# reactor.net
KiCad netlist of a schematic drawn in EAGLE
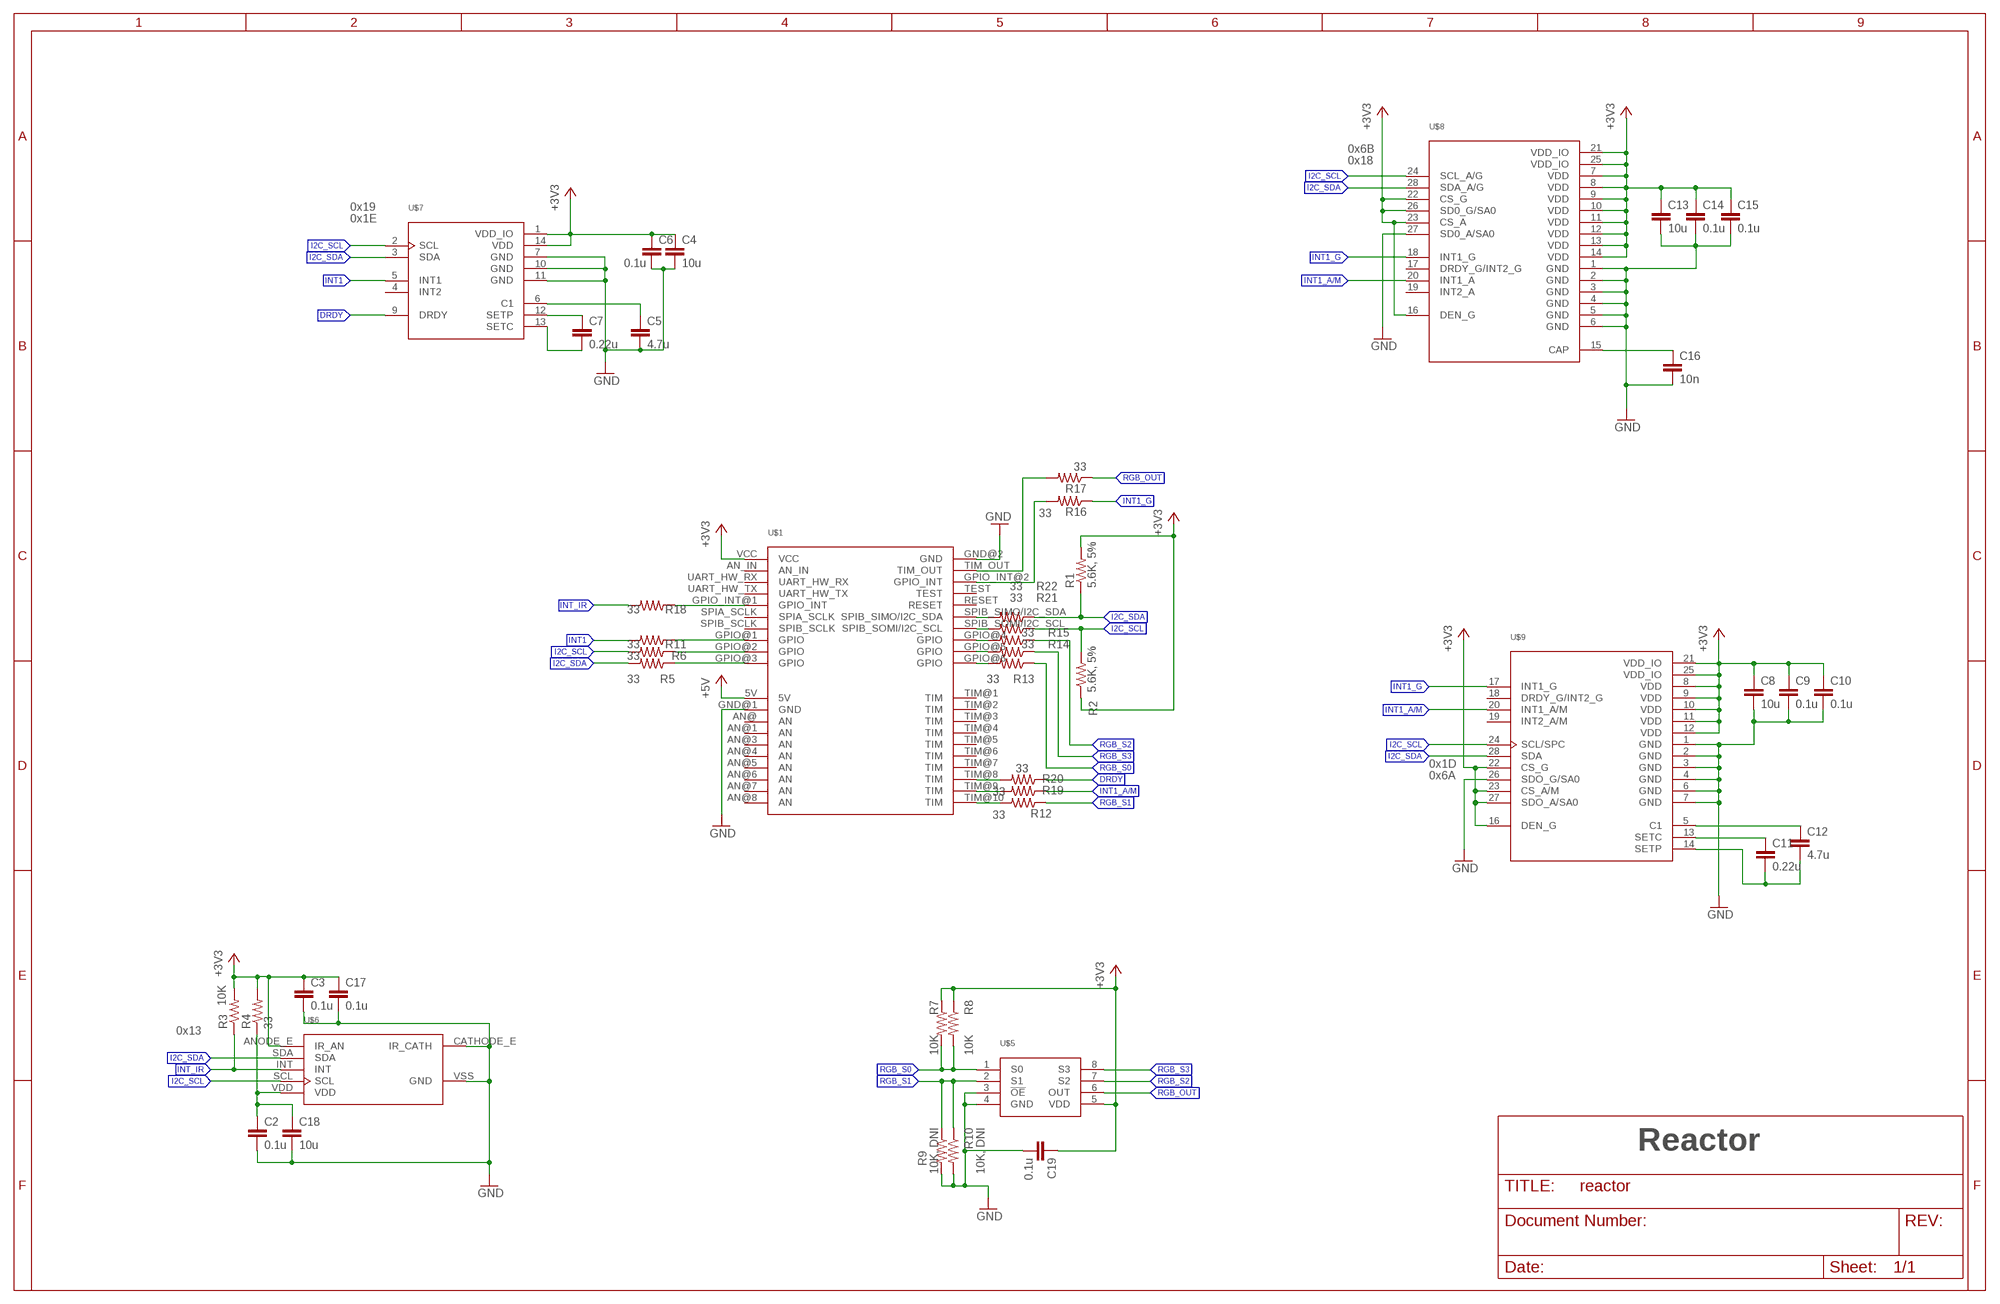
[diagram p0: schematic, sheet 1]

(export (version "E")
  (design (tool "Eeschema 10.0.6"))
  (components
    (comp (ref "C2")
      (value "0.1u")
      (footprint "eagle-import:C0603")
      (fields (field (name "MPN") "VJ0603V104ZXXCW1BC"))
      (libsource (lib "eagle-import") (part "C-EUC0603"))
    )
    (comp (ref "C3")
      (value "0.1u")
      (footprint "eagle-import:C0603")
      (fields (field (name "MPN") "VJ0603V104ZXXCW1BC"))
      (libsource (lib "eagle-import") (part "C-EUC0603"))
    )
    (comp (ref "C4")
      (value "10u")
      (footprint "eagle-import:C0603")
      (fields (field (name "MPN") "LMK107BBJ106MALT"))
      (libsource (lib "eagle-import") (part "C-EUC0603"))
    )
    (comp (ref "C5")
      (value "4.7u")
      (footprint "eagle-import:C0603")
      (fields (field (name "MPN") "GRM188F51A475ZE20J"))
      (libsource (lib "eagle-import") (part "C-EUC0603"))
    )
    (comp (ref "C6")
      (value "0.1u")
      (footprint "eagle-import:C0603")
      (fields (field (name "MPN") "VJ0603V104ZXXCW1BC"))
      (libsource (lib "eagle-import") (part "C-EUC0603"))
    )
    (comp (ref "C7")
      (value "0.22u")
      (footprint "eagle-import:C0603")
      (fields (field (name "MPN") "VJ0603V224MXJPW1BC"))
      (libsource (lib "eagle-import") (part "C-EUC0603"))
    )
    (comp (ref "C8")
      (value "10u")
      (footprint "eagle-import:C0603")
      (fields (field (name "MPN") "LMK107BBJ106MALT"))
      (libsource (lib "eagle-import") (part "C-EUC0603"))
    )
    (comp (ref "C9")
      (value "0.1u")
      (footprint "eagle-import:C0603")
      (fields (field (name "MPN") "VJ0603V104ZXXCW1BC"))
      (libsource (lib "eagle-import") (part "C-EUC0603"))
    )
    (comp (ref "C10")
      (value "0.1u")
      (footprint "eagle-import:C0603")
      (fields (field (name "MPN") "VJ0603V104ZXXCW1BC"))
      (libsource (lib "eagle-import") (part "C-EUC0603"))
    )
    (comp (ref "C11")
      (value "0.22u")
      (footprint "eagle-import:C0603")
      (fields (field (name "MPN") "VJ0603V224MXJPW1BC"))
      (libsource (lib "eagle-import") (part "C-EUC0603"))
    )
    (comp (ref "C12")
      (value "4.7u")
      (footprint "eagle-import:C0603")
      (fields (field (name "MPN") "GRM188F51A475ZE20J"))
      (libsource (lib "eagle-import") (part "C-EUC0603"))
    )
    (comp (ref "C13")
      (value "10u")
      (footprint "eagle-import:C0603")
      (fields (field (name "MPN") "LMK107BBJ106MALT"))
      (libsource (lib "eagle-import") (part "C-EUC0603"))
    )
    (comp (ref "C14")
      (value "0.1u")
      (footprint "eagle-import:C0603")
      (fields (field (name "MPN") "VJ0603V104ZXXCW1BC"))
      (libsource (lib "eagle-import") (part "C-EUC0603"))
    )
    (comp (ref "C15")
      (value "0.1u")
      (footprint "eagle-import:C0603")
      (fields (field (name "MPN") "VJ0603V104ZXXCW1BC"))
      (libsource (lib "eagle-import") (part "C-EUC0603"))
    )
    (comp (ref "C16")
      (value "10n")
      (footprint "eagle-import:C0603")
      (fields (field (name "MPN") "VJ0603Y103KXACW1BC"))
      (libsource (lib "eagle-import") (part "C-EUC0603"))
    )
    (comp (ref "C17")
      (value "0.1u")
      (footprint "eagle-import:C0603")
      (fields (field (name "MPN") "LMK107BBJ106MALT"))
      (libsource (lib "eagle-import") (part "C-EUC0603"))
    )
    (comp (ref "C18")
      (value "10u")
      (footprint "eagle-import:C0603")
      (fields (field (name "MPN") "LMK107BBJ106MALT"))
      (libsource (lib "eagle-import") (part "C-EUC0603"))
    )
    (comp (ref "C19")
      (value "0.1u")
      (footprint "eagle-import:C0603")
      (fields (field (name "MPN") "VJ0603V104ZXXCW1BC"))
      (libsource (lib "eagle-import") (part "C-EUC0603"))
    )
    (comp (ref "R1")
      (value "5.6K, 5%")
      (footprint "eagle-import:R0603")
      (fields (field (name "MPN") "RK73B1JTTDD562J"))
      (libsource (lib "eagle-import") (part "R-US_R0603"))
    )
    (comp (ref "R2")
      (value "5.6K, 5%")
      (footprint "eagle-import:R0603")
      (fields (field (name "MPN") "RK73B1JTTDD562J"))
      (libsource (lib "eagle-import") (part "R-US_R0603"))
    )
    (comp (ref "R3")
      (value "10K")
      (footprint "eagle-import:R0603")
      (fields (field (name "MPN") "WR06X1002FTL"))
      (libsource (lib "eagle-import") (part "R-US_R0603"))
    )
    (comp (ref "R4")
      (value "33")
      (footprint "eagle-import:R0603")
      (fields (field (name "MPN") "CR0402-JW-330GLF"))
      (libsource (lib "eagle-import") (part "R-US_R0603"))
    )
    (comp (ref "R5")
      (value "33")
      (footprint "eagle-import:R0603")
      (fields (field (name "MPN") "CR0402-JW-330GLF"))
      (libsource (lib "eagle-import") (part "R-US_R0603"))
    )
    (comp (ref "R6")
      (value "33")
      (footprint "eagle-import:R0603")
      (fields (field (name "MPN") "CR0402-JW-330GLF"))
      (libsource (lib "eagle-import") (part "R-US_R0603"))
    )
    (comp (ref "R7")
      (value "10K")
      (footprint "eagle-import:R0603")
      (fields (field (name "MPN") "WR06X1002FTL"))
      (libsource (lib "eagle-import") (part "R-US_R0603"))
    )
    (comp (ref "R8")
      (value "10K")
      (footprint "eagle-import:R0603")
      (fields (field (name "MPN") "WR06X1002FTL"))
      (libsource (lib "eagle-import") (part "R-US_R0603"))
    )
    (comp (ref "R9")
      (value "10K, DNI")
      (footprint "eagle-import:R0603")
      (fields (field (name "MPN") "WR06X1002FTL"))
      (libsource (lib "eagle-import") (part "R-US_R0603"))
    )
    (comp (ref "R10")
      (value "10K, DNI")
      (footprint "eagle-import:R0603")
      (fields (field (name "MPN") "WR06X1002FTL"))
      (libsource (lib "eagle-import") (part "R-US_R0603"))
    )
    (comp (ref "R11")
      (value "33")
      (footprint "eagle-import:R0603")
      (fields (field (name "MPN") "CR0402-JW-330GLF"))
      (libsource (lib "eagle-import") (part "R-US_R0603"))
    )
    (comp (ref "R12")
      (value "33")
      (footprint "eagle-import:R0603")
      (fields (field (name "MPN") "CR0402-JW-330GLF"))
      (libsource (lib "eagle-import") (part "R-US_R0603"))
    )
    (comp (ref "R13")
      (value "33")
      (footprint "eagle-import:R0603")
      (fields (field (name "MPN") "CR0402-JW-330GLF"))
      (libsource (lib "eagle-import") (part "R-US_R0603"))
    )
    (comp (ref "R14")
      (value "33")
      (footprint "eagle-import:R0603")
      (fields (field (name "MPN") "CR0402-JW-330GLF"))
      (libsource (lib "eagle-import") (part "R-US_R0603"))
    )
    (comp (ref "R15")
      (value "33")
      (footprint "eagle-import:R0603")
      (fields (field (name "MPN") "CR0402-JW-330GLF"))
      (libsource (lib "eagle-import") (part "R-US_R0603"))
    )
    (comp (ref "R16")
      (value "33")
      (footprint "eagle-import:R0603")
      (fields (field (name "MPN") "CR0402-JW-330GLF"))
      (libsource (lib "eagle-import") (part "R-US_R0603"))
    )
    (comp (ref "R17")
      (value "33")
      (footprint "eagle-import:R0603")
      (fields (field (name "MPN") "CR0402-JW-330GLF"))
      (libsource (lib "eagle-import") (part "R-US_R0603"))
    )
    (comp (ref "R18")
      (value "33")
      (footprint "eagle-import:R0603")
      (fields (field (name "MPN") "CR0402-JW-330GLF"))
      (libsource (lib "eagle-import") (part "R-US_R0603"))
    )
    (comp (ref "R19")
      (value "33")
      (footprint "eagle-import:R0603")
      (fields (field (name "MPN") "CR0402-JW-330GLF"))
      (libsource (lib "eagle-import") (part "R-US_R0603"))
    )
    (comp (ref "R20")
      (value "33")
      (footprint "eagle-import:R0603")
      (fields (field (name "MPN") "CR0402-JW-330GLF"))
      (libsource (lib "eagle-import") (part "R-US_R0603"))
    )
    (comp (ref "R21")
      (value "33")
      (footprint "eagle-import:R0603")
      (fields (field (name "MPN") "CR0402-JW-330GLF"))
      (libsource (lib "eagle-import") (part "R-US_R0603"))
    )
    (comp (ref "R22")
      (value "33")
      (footprint "eagle-import:R0603")
      (fields (field (name "MPN") "CR0402-JW-330GLF"))
      (libsource (lib "eagle-import") (part "R-US_R0603"))
    )
    (comp (ref "U$1")
      (value "LAUNCHPAD_BOOSTER_PACK")
      (footprint "eagle-import:LAUNCHPAD_BOOSTER_PACK")
      (libsource (lib "eagle-import") (part "LAUNCHPAD_BOOSTER_PACK"))
    )
    (comp (ref "U$5")
      (value "TCS32X0")
      (footprint "eagle-import:SOIC8")
      (libsource (lib "eagle-import") (part "TCS32X0"))
    )
    (comp (ref "U$6")
      (value "VCNL3020")
      (footprint "eagle-import:VCNL3020")
      (libsource (lib "eagle-import") (part "VCNL3020"))
    )
    (comp (ref "U$7")
      (value "LSM303DLHC")
      (footprint "eagle-import:LGA14")
      (libsource (lib "eagle-import") (part "LSM303DLHC"))
    )
    (comp (ref "U$8")
      (value "LSM330DLC")
      (footprint "eagle-import:LGA28-4X5")
      (libsource (lib "eagle-import") (part "LSM330DLC"))
    )
    (comp (ref "U$9")
      (value "LSM333D")
      (footprint "eagle-import:LGA28")
      (libsource (lib "eagle-import") (part "LSM333D"))
    )
  )
  (nets
    (net (code "1") (name "+3V3") (class "Default")
      (node (ref "C10") (pin "1") (pinfunction "1_1") (pintype "passive"))
      (node (ref "C13") (pin "1") (pinfunction "1_1") (pintype "passive"))
      (node (ref "C14") (pin "1") (pinfunction "1_1") (pintype "passive"))
      (node (ref "C15") (pin "1") (pinfunction "1_1") (pintype "passive"))
      (node (ref "C17") (pin "1") (pinfunction "1_1") (pintype "passive"))
      (node (ref "C19") (pin "1") (pinfunction "1_1") (pintype "passive"))
      (node (ref "C3") (pin "1") (pinfunction "1_1") (pintype "passive"))
      (node (ref "C4") (pin "1") (pinfunction "1_1") (pintype "passive"))
      (node (ref "C6") (pin "1") (pinfunction "1_1") (pintype "passive"))
      (node (ref "C8") (pin "1") (pinfunction "1_1") (pintype "passive"))
      (node (ref "C9") (pin "1") (pinfunction "1_1") (pintype "passive"))
      (node (ref "R1") (pin "2") (pinfunction "2_2") (pintype "passive"))
      (node (ref "R2") (pin "1") (pinfunction "1_1") (pintype "passive"))
      (node (ref "R3") (pin "2") (pinfunction "2_2") (pintype "passive"))
      (node (ref "R4") (pin "2") (pinfunction "2_2") (pintype "passive"))
      (node (ref "R7") (pin "1") (pinfunction "1_1") (pintype "passive"))
      (node (ref "R8") (pin "1") (pinfunction "1_1") (pintype "passive"))
      (node (ref "U$1") (pin "VCC") (pinfunction "VCC_VCC") (pintype "power_in"))
      (node (ref "U$5") (pin "5") (pinfunction "VDD_5") (pintype "power_in"))
      (node (ref "U$6") (pin "ANODE_E") (pinfunction "IR_AN_ANODE_E") (pintype "passive"))
      (node (ref "U$7") (pin "1") (pinfunction "VDD_IO_1") (pintype "power_in"))
      (node (ref "U$7") (pin "14") (pinfunction "VDD_14") (pintype "power_in"))
      (node (ref "U$8") (pin "10") (pinfunction "VDD_10") (pintype "power_in"))
      (node (ref "U$8") (pin "11") (pinfunction "VDD_11") (pintype "power_in"))
      (node (ref "U$8") (pin "12") (pinfunction "VDD_12") (pintype "power_in"))
      (node (ref "U$8") (pin "13") (pinfunction "VDD_13") (pintype "power_in"))
      (node (ref "U$8") (pin "14") (pinfunction "VDD_14") (pintype "power_in"))
      (node (ref "U$8") (pin "16") (pinfunction "DEN_G_16") (pintype "input"))
      (node (ref "U$8") (pin "21") (pinfunction "VDD_IO_21") (pintype "power_in"))
      (node (ref "U$8") (pin "22") (pinfunction "CS_G_22") (pintype "input"))
      (node (ref "U$8") (pin "23") (pinfunction "CS_A_23") (pintype "input"))
      (node (ref "U$8") (pin "25") (pinfunction "VDD_IO_25") (pintype "power_in"))
      (node (ref "U$8") (pin "26") (pinfunction "SD0_G/SA0_26") (pintype "bidirectional"))
      (node (ref "U$8") (pin "7") (pinfunction "VDD_7") (pintype "power_in"))
      (node (ref "U$8") (pin "8") (pinfunction "VDD_8") (pintype "power_in"))
      (node (ref "U$8") (pin "9") (pinfunction "VDD_9") (pintype "power_in"))
      (node (ref "U$9") (pin "10") (pinfunction "VDD_10") (pintype "power_in"))
      (node (ref "U$9") (pin "11") (pinfunction "VDD_11") (pintype "power_in"))
      (node (ref "U$9") (pin "12") (pinfunction "VDD_12") (pintype "power_in"))
      (node (ref "U$9") (pin "16") (pinfunction "DEN_G_16") (pintype "input"))
      (node (ref "U$9") (pin "21") (pinfunction "VDD_IO_21") (pintype "power_in"))
      (node (ref "U$9") (pin "22") (pinfunction "CS_G_22") (pintype "input"))
      (node (ref "U$9") (pin "23") (pinfunction "CS_A/M_23") (pintype "input"))
      (node (ref "U$9") (pin "25") (pinfunction "VDD_IO_25") (pintype "power_in"))
      (node (ref "U$9") (pin "27") (pinfunction "SDO_A/SA0_27") (pintype "bidirectional"))
      (node (ref "U$9") (pin "8") (pinfunction "VDD_8") (pintype "power_in"))
      (node (ref "U$9") (pin "9") (pinfunction "VDD_9") (pintype "power_in"))
    )
    (net (code "2") (name "+5V") (class "Default")
      (node (ref "U$1") (pin "5V") (pinfunction "5V_5V") (pintype "power_in"))
    )
    (net (code "3") (name "DRDY") (class "Default")
      (node (ref "R20") (pin "1") (pinfunction "1_1") (pintype "passive"))
      (node (ref "U$7") (pin "9") (pinfunction "DRDY_9") (pintype "output"))
    )
    (net (code "4") (name "GND") (class "Default")
      (node (ref "C10") (pin "2") (pinfunction "2_2") (pintype "passive"))
      (node (ref "C13") (pin "2") (pinfunction "2_2") (pintype "passive"))
      (node (ref "C14") (pin "2") (pinfunction "2_2") (pintype "passive"))
      (node (ref "C15") (pin "2") (pinfunction "2_2") (pintype "passive"))
      (node (ref "C16") (pin "2") (pinfunction "2_2") (pintype "passive"))
      (node (ref "C17") (pin "2") (pinfunction "2_2") (pintype "passive"))
      (node (ref "C18") (pin "2") (pinfunction "2_2") (pintype "passive"))
      (node (ref "C19") (pin "2") (pinfunction "2_2") (pintype "passive"))
      (node (ref "C2") (pin "2") (pinfunction "2_2") (pintype "passive"))
      (node (ref "C3") (pin "2") (pinfunction "2_2") (pintype "passive"))
      (node (ref "C4") (pin "2") (pinfunction "2_2") (pintype "passive"))
      (node (ref "C5") (pin "2") (pinfunction "2_2") (pintype "passive"))
      (node (ref "C6") (pin "2") (pinfunction "2_2") (pintype "passive"))
      (node (ref "C8") (pin "2") (pinfunction "2_2") (pintype "passive"))
      (node (ref "C9") (pin "2") (pinfunction "2_2") (pintype "passive"))
      (node (ref "R10") (pin "2") (pinfunction "2_2") (pintype "passive"))
      (node (ref "R9") (pin "2") (pinfunction "2_2") (pintype "passive"))
      (node (ref "U$1") (pin "GND@1") (pinfunction "GND_GND@1") (pintype "power_in"))
      (node (ref "U$1") (pin "GND@2") (pinfunction "GND_GND@2") (pintype "power_in"))
      (node (ref "U$5") (pin "3") (pinfunction "~{OE}_3") (pintype "input"))
      (node (ref "U$5") (pin "4") (pinfunction "GND_4") (pintype "power_in"))
      (node (ref "U$6") (pin "CATHODE_E") (pinfunction "IR_CATH_CATHODE_E") (pintype "passive"))
      (node (ref "U$6") (pin "VSS") (pinfunction "GND_VSS") (pintype "power_in"))
      (node (ref "U$7") (pin "10") (pinfunction "GND_10") (pintype "power_in"))
      (node (ref "U$7") (pin "11") (pinfunction "GND_11") (pintype "power_in"))
      (node (ref "U$7") (pin "7") (pinfunction "GND_7") (pintype "power_in"))
      (node (ref "U$8") (pin "1") (pinfunction "GND_1") (pintype "power_in"))
      (node (ref "U$8") (pin "2") (pinfunction "GND_2") (pintype "power_in"))
      (node (ref "U$8") (pin "27") (pinfunction "SD0_A/SA0_27") (pintype "bidirectional"))
      (node (ref "U$8") (pin "3") (pinfunction "GND_3") (pintype "power_in"))
      (node (ref "U$8") (pin "4") (pinfunction "GND_4") (pintype "power_in"))
      (node (ref "U$8") (pin "5") (pinfunction "GND_5") (pintype "power_in"))
      (node (ref "U$8") (pin "6") (pinfunction "GND_6") (pintype "power_in"))
      (node (ref "U$9") (pin "1") (pinfunction "GND_1") (pintype "power_in"))
      (node (ref "U$9") (pin "2") (pinfunction "GND_2") (pintype "power_in"))
      (node (ref "U$9") (pin "26") (pinfunction "SDO_G/SA0_26") (pintype "bidirectional"))
      (node (ref "U$9") (pin "3") (pinfunction "GND_3") (pintype "power_in"))
      (node (ref "U$9") (pin "4") (pinfunction "GND_4") (pintype "power_in"))
      (node (ref "U$9") (pin "6") (pinfunction "GND_6") (pintype "power_in"))
      (node (ref "U$9") (pin "7") (pinfunction "GND_7") (pintype "power_in"))
    )
    (net (code "5") (name "I2C_SCL") (class "Default")
      (node (ref "R2") (pin "2") (pinfunction "2_2") (pintype "passive"))
      (node (ref "R21") (pin "1") (pinfunction "1_1") (pintype "passive"))
      (node (ref "R6") (pin "2") (pinfunction "2_2") (pintype "passive"))
      (node (ref "U$6") (pin "SCL") (pinfunction "SCL_SCL") (pintype "input"))
      (node (ref "U$7") (pin "2") (pinfunction "SCL_2") (pintype "open_collector"))
      (node (ref "U$8") (pin "24") (pinfunction "SCL_A/G_24") (pintype "open_collector"))
      (node (ref "U$9") (pin "24") (pinfunction "SCL/SPC_24") (pintype "open_collector"))
    )
    (net (code "6") (name "I2C_SDA") (class "Default")
      (node (ref "R1") (pin "1") (pinfunction "1_1") (pintype "passive"))
      (node (ref "R22") (pin "1") (pinfunction "1_1") (pintype "passive"))
      (node (ref "R5") (pin "2") (pinfunction "2_2") (pintype "passive"))
      (node (ref "U$6") (pin "SDA") (pinfunction "SDA_SDA") (pintype "bidirectional"))
      (node (ref "U$7") (pin "3") (pinfunction "SDA_3") (pintype "open_collector"))
      (node (ref "U$8") (pin "28") (pinfunction "SDA_A/G_28") (pintype "open_collector"))
      (node (ref "U$9") (pin "28") (pinfunction "SDA_28") (pintype "open_collector"))
    )
    (net (code "7") (name "INT1") (class "Default")
      (node (ref "R11") (pin "2") (pinfunction "2_2") (pintype "passive"))
      (node (ref "U$7") (pin "5") (pinfunction "INT1_5") (pintype "output"))
    )
    (net (code "8") (name "INT1_A{slash}M") (class "Default")
      (node (ref "R19") (pin "1") (pinfunction "1_1") (pintype "passive"))
      (node (ref "U$8") (pin "20") (pinfunction "INT1_A_20") (pintype "output"))
      (node (ref "U$9") (pin "20") (pinfunction "INT1_A/M_20") (pintype "output"))
    )
    (net (code "9") (name "INT1_G") (class "Default")
      (node (ref "R16") (pin "1") (pinfunction "1_1") (pintype "passive"))
      (node (ref "U$8") (pin "18") (pinfunction "INT1_G_18") (pintype "output"))
      (node (ref "U$9") (pin "17") (pinfunction "INT1_G_17") (pintype "output"))
    )
    (net (code "10") (name "INT_IR") (class "Default")
      (node (ref "R18") (pin "2") (pinfunction "2_2") (pintype "passive"))
      (node (ref "R3") (pin "1") (pinfunction "1_1") (pintype "passive"))
      (node (ref "U$6") (pin "INT") (pinfunction "INT_INT") (pintype "output"))
    )
    (net (code "11") (name "Net-(C18-Pad1)") (class "Default")
      (node (ref "C18") (pin "1") (pinfunction "1_1") (pintype "passive"))
      (node (ref "C2") (pin "1") (pinfunction "1_1") (pintype "passive"))
      (node (ref "R4") (pin "1") (pinfunction "1_1") (pintype "passive"))
      (node (ref "U$6") (pin "VDD") (pinfunction "VDD_VDD") (pintype "power_in"))
    )
    (net (code "12") (name "Net-(R5-Pad1)") (class "Default")
      (node (ref "R5") (pin "1") (pinfunction "1_1") (pintype "passive"))
      (node (ref "U$1") (pin "GPIO@3") (pinfunction "GPIO_GPIO@3") (pintype "bidirectional"))
    )
    (net (code "13") (name "Net-(R6-Pad1)") (class "Default")
      (node (ref "R6") (pin "1") (pinfunction "1_1") (pintype "passive"))
      (node (ref "U$1") (pin "GPIO@2") (pinfunction "GPIO_GPIO@2") (pintype "bidirectional"))
    )
    (net (code "14") (name "Net-(R11-Pad1)") (class "Default")
      (node (ref "R11") (pin "1") (pinfunction "1_1") (pintype "passive"))
      (node (ref "U$1") (pin "GPIO@1") (pinfunction "GPIO_GPIO@1") (pintype "bidirectional"))
    )
    (net (code "15") (name "Net-(R12-Pad2)") (class "Default")
      (node (ref "R12") (pin "2") (pinfunction "2_2") (pintype "passive"))
      (node (ref "U$1") (pin "TIM@10") (pinfunction "TIM_TIM@10") (pintype "bidirectional"))
    )
    (net (code "16") (name "Net-(R13-Pad2)") (class "Default")
      (node (ref "R13") (pin "2") (pinfunction "2_2") (pintype "passive"))
      (node (ref "U$1") (pin "GPIO@6") (pinfunction "GPIO_GPIO@6") (pintype "bidirectional"))
    )
    (net (code "17") (name "Net-(R14-Pad2)") (class "Default")
      (node (ref "R14") (pin "2") (pinfunction "2_2") (pintype "passive"))
      (node (ref "U$1") (pin "GPIO@5") (pinfunction "GPIO_GPIO@5") (pintype "bidirectional"))
    )
    (net (code "18") (name "Net-(R15-Pad2)") (class "Default")
      (node (ref "R15") (pin "2") (pinfunction "2_2") (pintype "passive"))
      (node (ref "U$1") (pin "GPIO@4") (pinfunction "GPIO_GPIO@4") (pintype "bidirectional"))
    )
    (net (code "19") (name "Net-(R16-Pad2)") (class "Default")
      (node (ref "R16") (pin "2") (pinfunction "2_2") (pintype "passive"))
      (node (ref "U$1") (pin "GPIO_INT@2") (pinfunction "GPIO_INT_GPIO_INT@2") (pintype "bidirectional"))
    )
    (net (code "20") (name "Net-(R17-Pad2)") (class "Default")
      (node (ref "R17") (pin "2") (pinfunction "2_2") (pintype "passive"))
      (node (ref "U$1") (pin "TIM_OUT") (pinfunction "TIM_OUT_TIM_OUT") (pintype "bidirectional"))
    )
    (net (code "21") (name "Net-(R18-Pad1)") (class "Default")
      (node (ref "R18") (pin "1") (pinfunction "1_1") (pintype "passive"))
      (node (ref "U$1") (pin "GPIO_INT@1") (pinfunction "GPIO_INT_GPIO_INT@1") (pintype "bidirectional"))
    )
    (net (code "22") (name "Net-(R19-Pad2)") (class "Default")
      (node (ref "R19") (pin "2") (pinfunction "2_2") (pintype "passive"))
      (node (ref "U$1") (pin "TIM@9") (pinfunction "TIM_TIM@9") (pintype "bidirectional"))
    )
    (net (code "23") (name "Net-(R20-Pad2)") (class "Default")
      (node (ref "R20") (pin "2") (pinfunction "2_2") (pintype "passive"))
      (node (ref "U$1") (pin "TIM@8") (pinfunction "TIM_TIM@8") (pintype "bidirectional"))
    )
    (net (code "24") (name "Net-(R21-Pad2)") (class "Default")
      (node (ref "R21") (pin "2") (pinfunction "2_2") (pintype "passive"))
      (node (ref "U$1") (pin "SPIB_SOMI/I2C_SCL") (pinfunction "SPIB_SOMI/I2C_SCL_SPIB_SOMI/I2C_SCL") (pintype "bidirectional"))
    )
    (net (code "25") (name "Net-(R22-Pad2)") (class "Default")
      (node (ref "R22") (pin "2") (pinfunction "2_2") (pintype "passive"))
      (node (ref "U$1") (pin "SPIB_SIMO/I2C_SDA") (pinfunction "SPIB_SIMO/I2C_SDA_SPIB_SIMO/I2C_SDA") (pintype "bidirectional"))
    )
    (net (code "26") (name "Net-(U$7-C1)") (class "Default")
      (node (ref "C5") (pin "1") (pinfunction "1_1") (pintype "passive"))
      (node (ref "U$7") (pin "6") (pinfunction "C1_6") (pintype "passive"))
    )
    (net (code "27") (name "Net-(U$7-SETC)") (class "Default")
      (node (ref "C7") (pin "2") (pinfunction "2_2") (pintype "passive"))
      (node (ref "U$7") (pin "13") (pinfunction "SETC_13") (pintype "passive"))
    )
    (net (code "28") (name "Net-(U$7-SETP)") (class "Default")
      (node (ref "C7") (pin "1") (pinfunction "1_1") (pintype "passive"))
      (node (ref "U$7") (pin "12") (pinfunction "SETP_12") (pintype "passive"))
    )
    (net (code "29") (name "Net-(U$8-CAP)") (class "Default")
      (node (ref "C16") (pin "1") (pinfunction "1_1") (pintype "passive"))
      (node (ref "U$8") (pin "15") (pinfunction "CAP_15") (pintype "passive"))
    )
    (net (code "30") (name "Net-(U$9-C1)") (class "Default")
      (node (ref "C12") (pin "1") (pinfunction "1_1") (pintype "passive"))
      (node (ref "U$9") (pin "5") (pinfunction "C1_5") (pintype "passive"))
    )
    (net (code "31") (name "Net-(U$9-SETC)") (class "Default")
      (node (ref "C11") (pin "1") (pinfunction "1_1") (pintype "passive"))
      (node (ref "U$9") (pin "13") (pinfunction "SETC_13") (pintype "passive"))
    )
    (net (code "32") (name "Net-(U$9-SETP)") (class "Default")
      (node (ref "C11") (pin "2") (pinfunction "2_2") (pintype "passive"))
      (node (ref "C12") (pin "2") (pinfunction "2_2") (pintype "passive"))
      (node (ref "U$9") (pin "14") (pinfunction "SETP_14") (pintype "passive"))
    )
    (net (code "33") (name "RGB_OUT") (class "Default")
      (node (ref "R17") (pin "1") (pinfunction "1_1") (pintype "passive"))
      (node (ref "U$5") (pin "6") (pinfunction "OUT_6") (pintype "output"))
    )
    (net (code "34") (name "RGB_S0") (class "Default")
      (node (ref "R13") (pin "1") (pinfunction "1_1") (pintype "passive"))
      (node (ref "R7") (pin "2") (pinfunction "2_2") (pintype "passive"))
      (node (ref "R8") (pin "2") (pinfunction "2_2") (pintype "passive"))
      (node (ref "U$5") (pin "1") (pinfunction "S0_1") (pintype "input"))
    )
    (net (code "35") (name "RGB_S1") (class "Default")
      (node (ref "R10") (pin "1") (pinfunction "1_1") (pintype "passive"))
      (node (ref "R12") (pin "1") (pinfunction "1_1") (pintype "passive"))
      (node (ref "R9") (pin "1") (pinfunction "1_1") (pintype "passive"))
      (node (ref "U$5") (pin "2") (pinfunction "S1_2") (pintype "input"))
    )
    (net (code "36") (name "RGB_S2") (class "Default")
      (node (ref "R15") (pin "1") (pinfunction "1_1") (pintype "passive"))
      (node (ref "U$5") (pin "7") (pinfunction "S2_7") (pintype "input"))
    )
    (net (code "37") (name "RGB_S3") (class "Default")
      (node (ref "R14") (pin "1") (pinfunction "1_1") (pintype "passive"))
      (node (ref "U$5") (pin "8") (pinfunction "S3_8") (pintype "input"))
    )
    (net (code "38") (name "unconnected-(U$1-AN-PadAN@)") (class "Default")
      (node (ref "U$1") (pin "AN@") (pinfunction "AN_AN@") (pintype "bidirectional"))
    )
    (net (code "39") (name "unconnected-(U$1-AN-PadAN@1)") (class "Default")
      (node (ref "U$1") (pin "AN@1") (pinfunction "AN_AN@1") (pintype "bidirectional"))
    )
    (net (code "40") (name "unconnected-(U$1-AN-PadAN@3)") (class "Default")
      (node (ref "U$1") (pin "AN@3") (pinfunction "AN_AN@3") (pintype "bidirectional"))
    )
    (net (code "41") (name "unconnected-(U$1-AN-PadAN@4)") (class "Default")
      (node (ref "U$1") (pin "AN@4") (pinfunction "AN_AN@4") (pintype "bidirectional"))
    )
    (net (code "42") (name "unconnected-(U$1-AN-PadAN@5)") (class "Default")
      (node (ref "U$1") (pin "AN@5") (pinfunction "AN_AN@5") (pintype "bidirectional"))
    )
    (net (code "43") (name "unconnected-(U$1-AN-PadAN@6)") (class "Default")
      (node (ref "U$1") (pin "AN@6") (pinfunction "AN_AN@6") (pintype "bidirectional"))
    )
    (net (code "44") (name "unconnected-(U$1-AN-PadAN@7)") (class "Default")
      (node (ref "U$1") (pin "AN@7") (pinfunction "AN_AN@7") (pintype "bidirectional"))
    )
    (net (code "45") (name "unconnected-(U$1-AN-PadAN@8)") (class "Default")
      (node (ref "U$1") (pin "AN@8") (pinfunction "AN_AN@8") (pintype "bidirectional"))
    )
    (net (code "46") (name "unconnected-(U$1-PadAN_IN)") (class "Default")
      (node (ref "U$1") (pin "AN_IN") (pinfunction "AN_IN_AN_IN") (pintype "bidirectional"))
    )
    (net (code "47") (name "unconnected-(U$1-PadRESET)") (class "Default")
      (node (ref "U$1") (pin "RESET") (pinfunction "RESET_RESET") (pintype "bidirectional"))
    )
    (net (code "48") (name "unconnected-(U$1-PadSPIA_SCLK)") (class "Default")
      (node (ref "U$1") (pin "SPIA_SCLK") (pinfunction "SPIA_SCLK_SPIA_SCLK") (pintype "bidirectional"))
    )
    (net (code "49") (name "unconnected-(U$1-PadSPIB_SCLK)") (class "Default")
      (node (ref "U$1") (pin "SPIB_SCLK") (pinfunction "SPIB_SCLK_SPIB_SCLK") (pintype "bidirectional"))
    )
    (net (code "50") (name "unconnected-(U$1-PadTEST)") (class "Default")
      (node (ref "U$1") (pin "TEST") (pinfunction "TEST_TEST") (pintype "bidirectional"))
    )
    (net (code "51") (name "unconnected-(U$1-PadUART_HW_RX)") (class "Default")
      (node (ref "U$1") (pin "UART_HW_RX") (pinfunction "UART_HW_RX_UART_HW_RX") (pintype "bidirectional"))
    )
    (net (code "52") (name "unconnected-(U$1-PadUART_HW_TX)") (class "Default")
      (node (ref "U$1") (pin "UART_HW_TX") (pinfunction "UART_HW_TX_UART_HW_TX") (pintype "bidirectional"))
    )
    (net (code "53") (name "unconnected-(U$1-TIM-PadTIM@1)") (class "Default")
      (node (ref "U$1") (pin "TIM@1") (pinfunction "TIM_TIM@1") (pintype "bidirectional"))
    )
    (net (code "54") (name "unconnected-(U$1-TIM-PadTIM@2)") (class "Default")
      (node (ref "U$1") (pin "TIM@2") (pinfunction "TIM_TIM@2") (pintype "bidirectional"))
    )
    (net (code "55") (name "unconnected-(U$1-TIM-PadTIM@3)") (class "Default")
      (node (ref "U$1") (pin "TIM@3") (pinfunction "TIM_TIM@3") (pintype "bidirectional"))
    )
    (net (code "56") (name "unconnected-(U$1-TIM-PadTIM@4)") (class "Default")
      (node (ref "U$1") (pin "TIM@4") (pinfunction "TIM_TIM@4") (pintype "bidirectional"))
    )
    (net (code "57") (name "unconnected-(U$1-TIM-PadTIM@5)") (class "Default")
      (node (ref "U$1") (pin "TIM@5") (pinfunction "TIM_TIM@5") (pintype "bidirectional"))
    )
    (net (code "58") (name "unconnected-(U$1-TIM-PadTIM@6)") (class "Default")
      (node (ref "U$1") (pin "TIM@6") (pinfunction "TIM_TIM@6") (pintype "bidirectional"))
    )
    (net (code "59") (name "unconnected-(U$1-TIM-PadTIM@7)") (class "Default")
      (node (ref "U$1") (pin "TIM@7") (pinfunction "TIM_TIM@7") (pintype "bidirectional"))
    )
    (net (code "60") (name "unconnected-(U$7-INT2-Pad4)") (class "Default")
      (node (ref "U$7") (pin "4") (pinfunction "INT2_4") (pintype "output"))
    )
    (net (code "61") (name "unconnected-(U$8-DRDY_G{slash}INT2_G-Pad17)") (class "Default")
      (node (ref "U$8") (pin "17") (pinfunction "DRDY_G/INT2_G_17") (pintype "output"))
    )
    (net (code "62") (name "unconnected-(U$8-INT2_A-Pad19)") (class "Default")
      (node (ref "U$8") (pin "19") (pinfunction "INT2_A_19") (pintype "output"))
    )
    (net (code "63") (name "unconnected-(U$9-DRDY_G{slash}INT2_G-Pad18)") (class "Default")
      (node (ref "U$9") (pin "18") (pinfunction "DRDY_G/INT2_G_18") (pintype "output"))
    )
    (net (code "64") (name "unconnected-(U$9-INT2_A{slash}M-Pad19)") (class "Default")
      (node (ref "U$9") (pin "19") (pinfunction "INT2_A/M_19") (pintype "output"))
    )
  )
)
